# VGA.net
KiCad netlist of a schematic drawn in Altium Designer
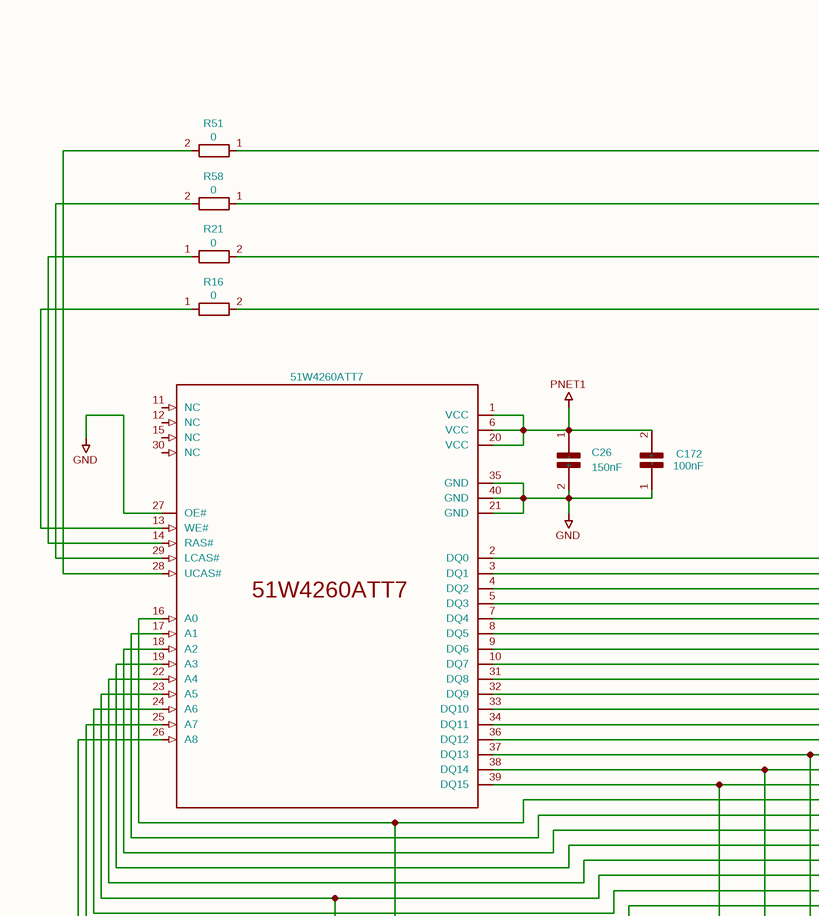
[diagram p0: VGA.SchDoc, top left]
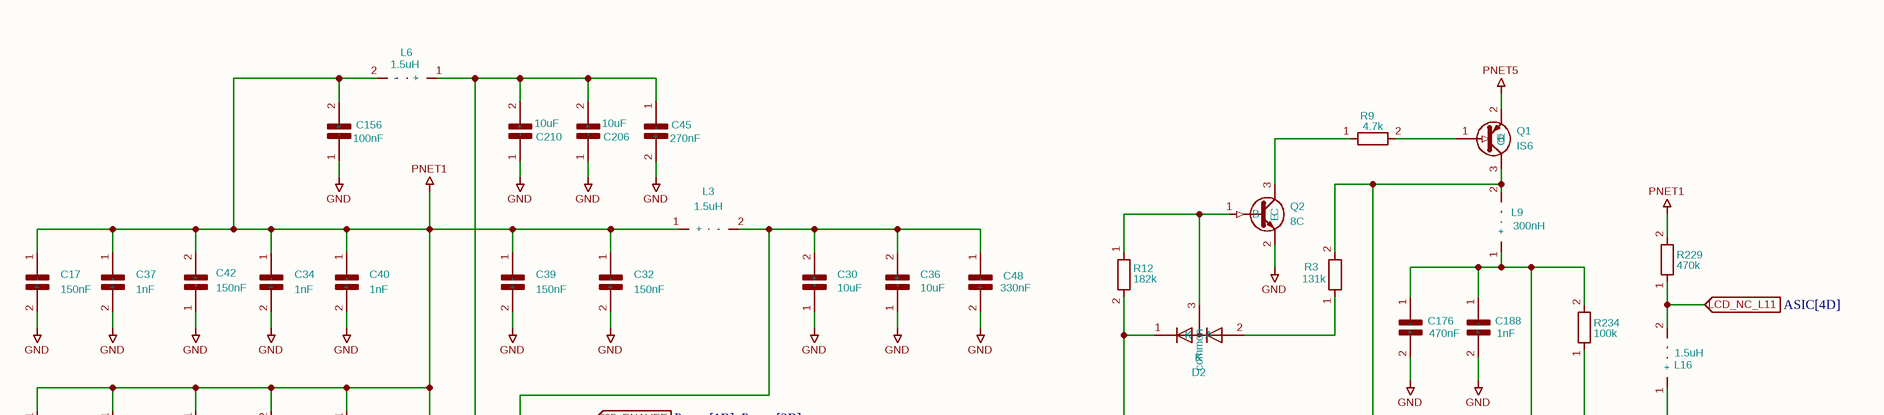
[diagram p1: VGA.SchDoc, top right]
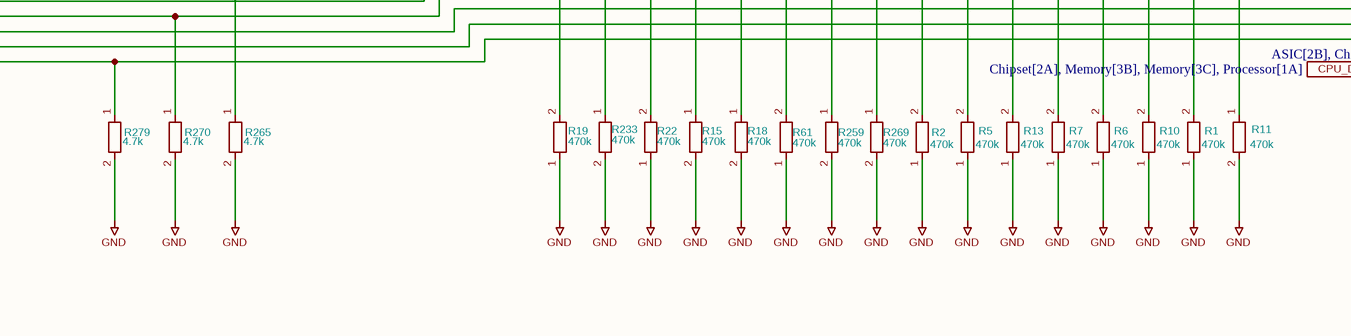
[diagram p2: VGA.SchDoc, bottom left]
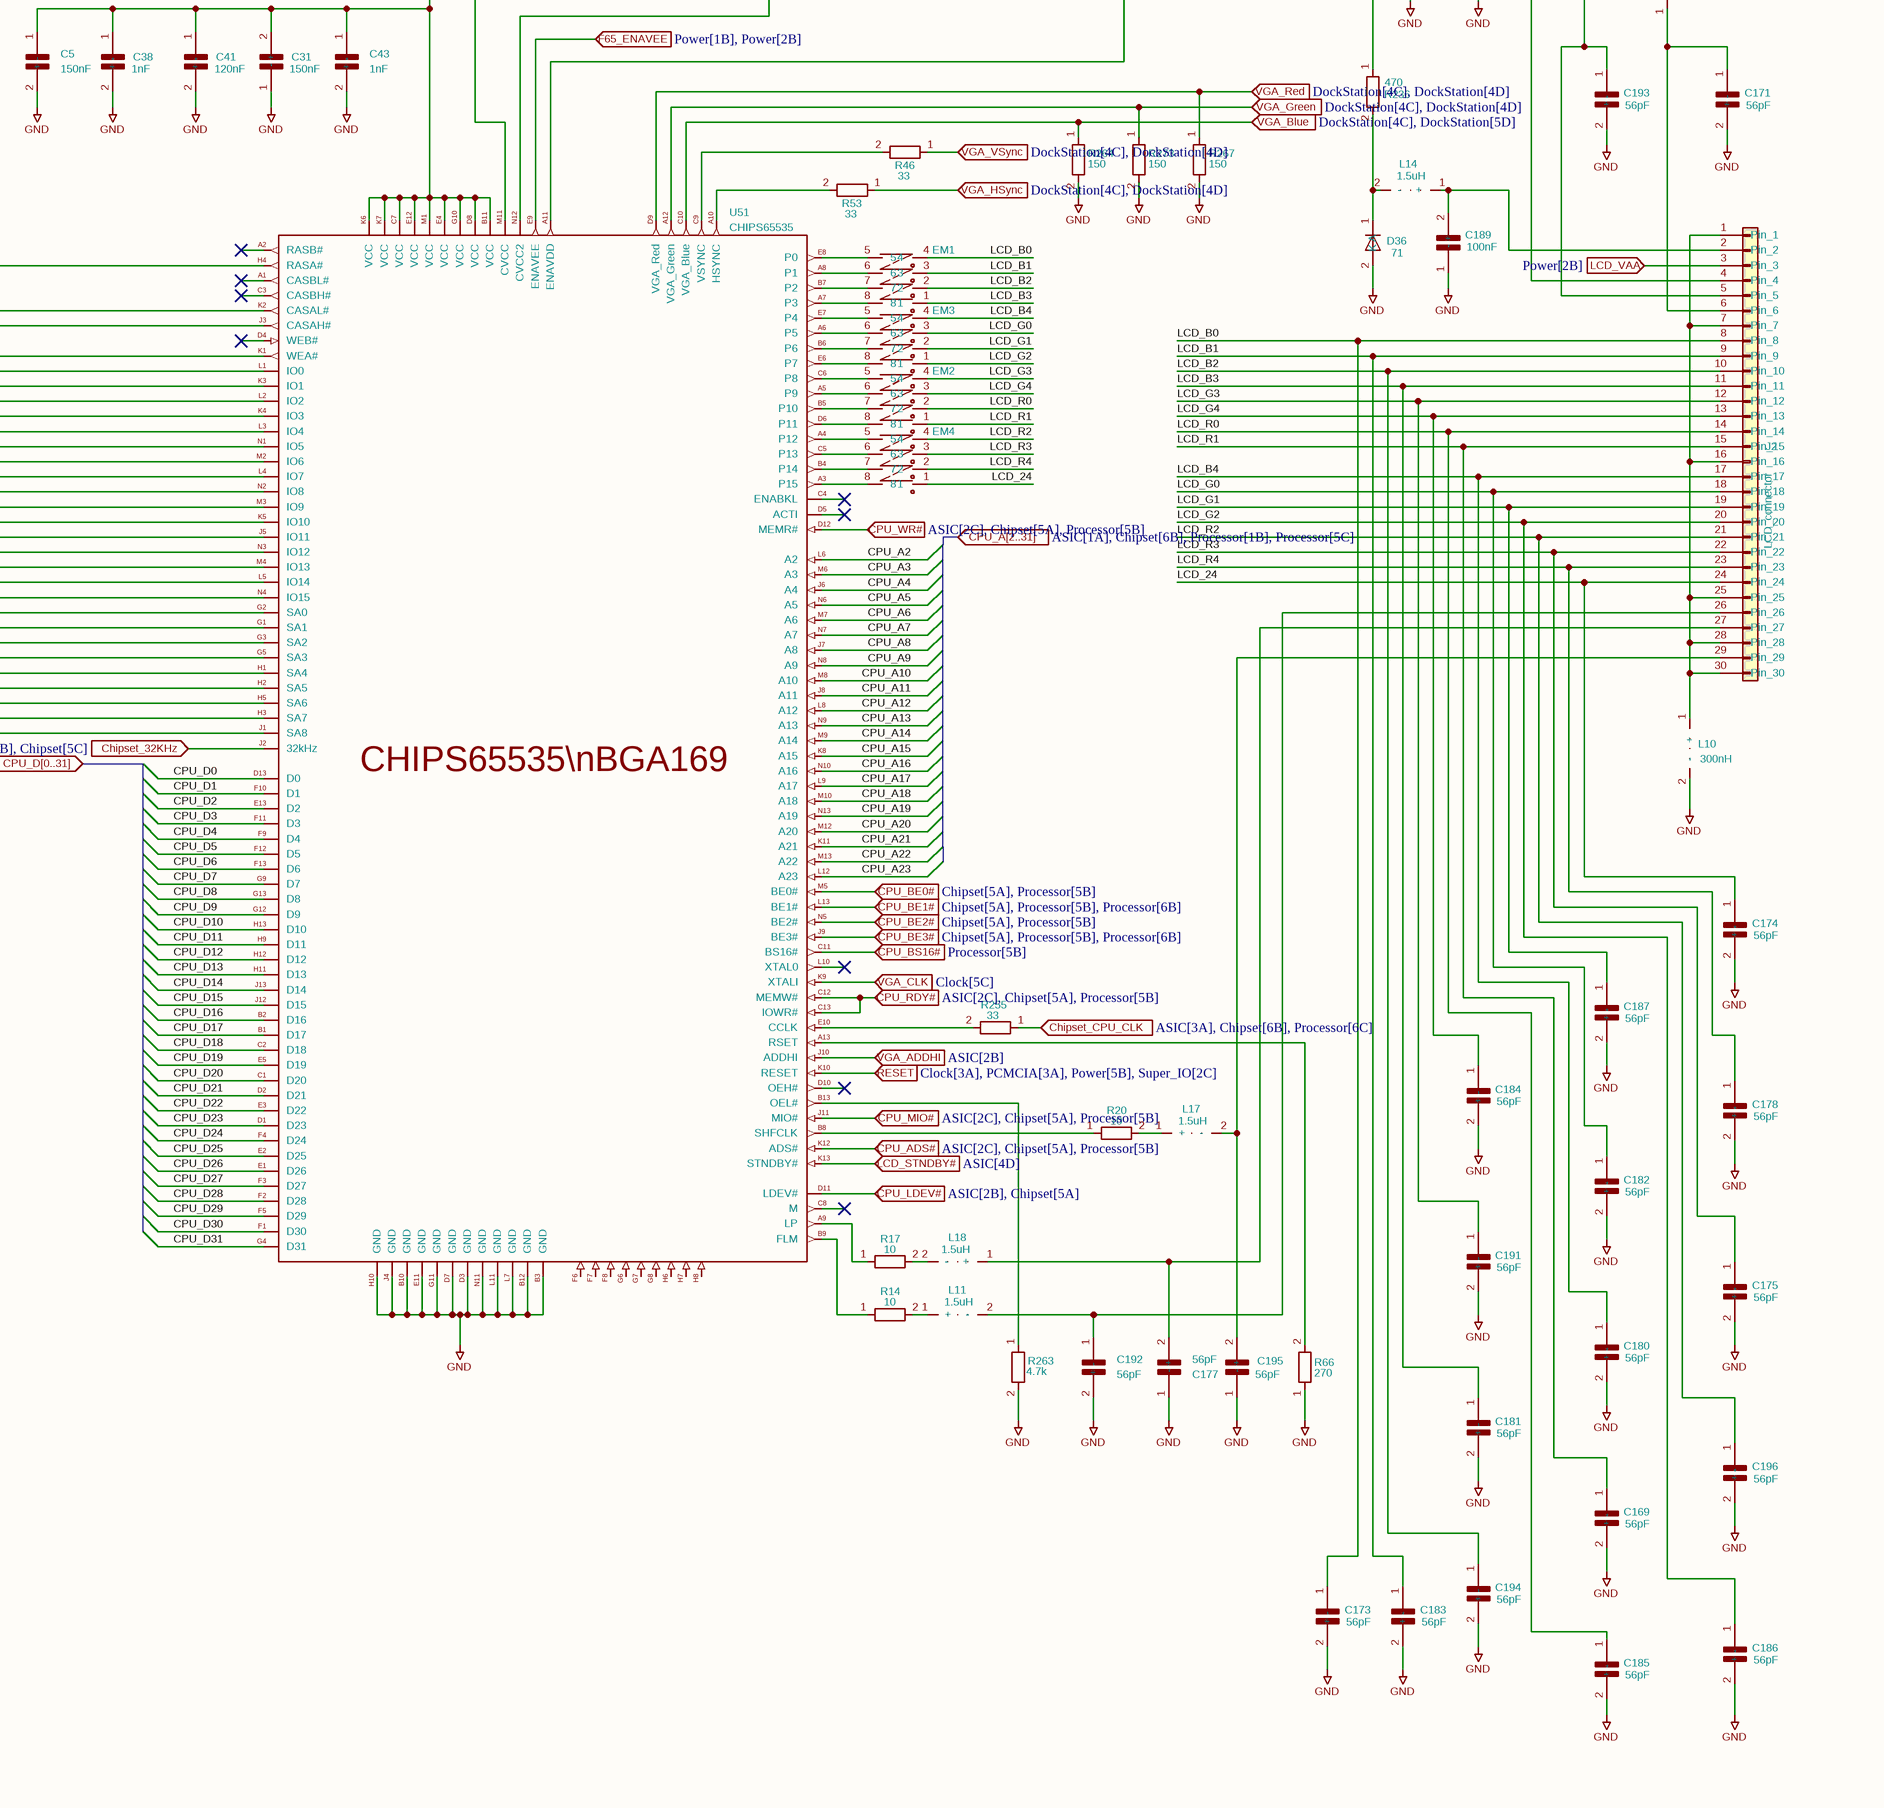
[diagram p3: VGA.SchDoc, bottom right]

(export (version "E")
  (design (tool "Eeschema 10.0.6"))
  (components
    (comp (ref "C5")
      (value "150nF")
      (footprint "C_0402_1005Metric")
      (libsource (lib "PCM_Elektuur") (part "C"))
    )
    (comp (ref "C17")
      (value "150nF")
      (footprint "C_0402_1005Metric")
      (libsource (lib "PCM_Elektuur") (part "C"))
    )
    (comp (ref "C26")
      (value "150nF")
      (footprint "C_0402_1005Metric")
      (libsource (lib "PCM_Elektuur") (part "C"))
    )
    (comp (ref "C30") (value "10uF") (footprint "C_1206_3216Metric") (libsource (lib "") (part "C_1")))
    (comp (ref "C31") (value "150nF") (footprint "C_0402_1005Metric") (libsource (lib "") (part "C_1")))
    (comp (ref "C32")
      (value "150nF")
      (footprint "C_0402_1005Metric")
      (libsource (lib "PCM_Elektuur") (part "C"))
    )
    (comp (ref "C34")
      (value "1nF")
      (footprint "C_0402_1005Metric")
      (libsource (lib "PCM_Elektuur") (part "C"))
    )
    (comp (ref "C36") (value "10uF") (footprint "C_1206_3216Metric") (libsource (lib "") (part "C_1")))
    (comp (ref "C37")
      (value "1nF")
      (footprint "C_0402_1005Metric")
      (libsource (lib "PCM_Elektuur") (part "C"))
    )
    (comp (ref "C38")
      (value "1nF")
      (footprint "C_0402_1005Metric")
      (libsource (lib "PCM_Elektuur") (part "C"))
    )
    (comp (ref "C39")
      (value "150nF")
      (footprint "C_0402_1005Metric")
      (libsource (lib "PCM_Elektuur") (part "C"))
    )
    (comp (ref "C40")
      (value "1nF")
      (footprint "C_0402_1005Metric")
      (libsource (lib "PCM_Elektuur") (part "C"))
    )
    (comp (ref "C41")
      (value "120nF")
      (footprint "C_0402_1005Metric")
      (libsource (lib "PCM_Elektuur") (part "C"))
    )
    (comp (ref "C42") (value "150nF") (footprint "C_0402_1005Metric") (libsource (lib "") (part "C_1")))
    (comp (ref "C43")
      (value "1nF")
      (footprint "C_0402_1005Metric")
      (libsource (lib "PCM_Elektuur") (part "C"))
    )
    (comp (ref "C45")
      (value "270nF")
      (footprint "C_0603_1608Metric")
      (libsource (lib "PCM_Elektuur") (part "C"))
    )
    (comp (ref "C48")
      (value "330nF")
      (footprint "C_0402_1005Metric")
      (libsource (lib "PCM_Elektuur") (part "C"))
    )
    (comp (ref "C156") (value "100nF") (footprint "C_0402_1005Metric") (libsource (lib "") (part "C_1")))
    (comp (ref "C169")
      (value "56pF")
      (footprint "C_0402_1005Metric")
      (libsource (lib "PCM_Elektuur") (part "C"))
    )
    (comp (ref "C171")
      (value "56pF")
      (footprint "C_0402_1005Metric")
      (libsource (lib "PCM_Elektuur") (part "C"))
    )
    (comp (ref "C172") (value "100nF") (footprint "C_0402_1005Metric") (libsource (lib "") (part "C_1")))
    (comp (ref "C173")
      (value "56pF")
      (footprint "C_0402_1005Metric")
      (libsource (lib "PCM_Elektuur") (part "C"))
    )
    (comp (ref "C174")
      (value "56pF")
      (footprint "C_0402_1005Metric")
      (libsource (lib "PCM_Elektuur") (part "C"))
    )
    (comp (ref "C175")
      (value "56pF")
      (footprint "C_0402_1005Metric")
      (libsource (lib "PCM_Elektuur") (part "C"))
    )
    (comp (ref "C176")
      (value "470nF")
      (footprint "C_0603_1608Metric")
      (libsource (lib "PCM_Elektuur") (part "C"))
    )
    (comp (ref "C177") (value "56pF") (footprint "C_0402_1005Metric") (libsource (lib "") (part "C_1")))
    (comp (ref "C178")
      (value "56pF")
      (footprint "C_0402_1005Metric")
      (libsource (lib "PCM_Elektuur") (part "C"))
    )
    (comp (ref "C180")
      (value "56pF")
      (footprint "C_0402_1005Metric")
      (libsource (lib "PCM_Elektuur") (part "C"))
    )
    (comp (ref "C181")
      (value "56pF")
      (footprint "C_0402_1005Metric")
      (libsource (lib "PCM_Elektuur") (part "C"))
    )
    (comp (ref "C182")
      (value "56pF")
      (footprint "C_0402_1005Metric")
      (libsource (lib "PCM_Elektuur") (part "C"))
    )
    (comp (ref "C183")
      (value "56pF")
      (footprint "C_0402_1005Metric")
      (libsource (lib "PCM_Elektuur") (part "C"))
    )
    (comp (ref "C184")
      (value "56pF")
      (footprint "C_0402_1005Metric")
      (libsource (lib "PCM_Elektuur") (part "C"))
    )
    (comp (ref "C185")
      (value "56pF")
      (footprint "C_0402_1005Metric")
      (libsource (lib "PCM_Elektuur") (part "C"))
    )
    (comp (ref "C186")
      (value "56pF")
      (footprint "C_0402_1005Metric")
      (libsource (lib "PCM_Elektuur") (part "C"))
    )
    (comp (ref "C187")
      (value "56pF")
      (footprint "C_0402_1005Metric")
      (libsource (lib "PCM_Elektuur") (part "C"))
    )
    (comp (ref "C188")
      (value "1nF")
      (footprint "C_0402_1005Metric")
      (libsource (lib "PCM_Elektuur") (part "C"))
    )
    (comp (ref "C189") (value "100nF") (footprint "C_0402_1005Metric") (libsource (lib "") (part "C_1")))
    (comp (ref "C191")
      (value "56pF")
      (footprint "C_0402_1005Metric")
      (libsource (lib "PCM_Elektuur") (part "C"))
    )
    (comp (ref "C192")
      (value "56pF")
      (footprint "C_0402_1005Metric")
      (libsource (lib "PCM_Elektuur") (part "C"))
    )
    (comp (ref "C193")
      (value "56pF")
      (footprint "C_0402_1005Metric")
      (libsource (lib "PCM_Elektuur") (part "C"))
    )
    (comp (ref "C194")
      (value "56pF")
      (footprint "C_0402_1005Metric")
      (libsource (lib "PCM_Elektuur") (part "C"))
    )
    (comp (ref "C195") (value "56pF") (footprint "C_0402_1005Metric") (libsource (lib "") (part "C_1")))
    (comp (ref "C196")
      (value "56pF")
      (footprint "C_0402_1005Metric")
      (libsource (lib "PCM_Elektuur") (part "C"))
    )
    (comp (ref "C206") (value "10uF") (footprint "C_1206_3216Metric") (libsource (lib "") (part "C_1")))
    (comp (ref "C210") (value "10uF") (footprint "C_1206_3216Metric") (libsource (lib "") (part "C_1")))
    (comp (ref "D2") (value "K") (footprint "SOT-416L") (libsource (lib "Device") (part "D_Dual_Series_KAC")))
    (comp (ref "D36") (value "71") (footprint "D_0603_1608Metric") (libsource (lib "Device") (part "D")))
    (comp (ref "EM1")
      (value "R-array")
      (footprint "R-array")
      (libsource (lib "PC110") (part "EMI_filter_Array"))
    )
    (comp (ref "EM2")
      (value "R-array")
      (footprint "R-array")
      (libsource (lib "*") (part "EMI_filter_Array_2"))
    )
    (comp (ref "EM3")
      (value "R-array")
      (footprint "R-array")
      (libsource (lib "*") (part "EMI_filter_Array_1"))
    )
    (comp (ref "EM4")
      (value "R-array")
      (footprint "R-array")
      (libsource (lib "*") (part "EMI_filter_Array_3"))
    )
    (comp (ref "J2")
      (value "LCD_connector")
      (footprint "LCD_connector")
      (libsource (lib "Connector_Generic") (part "Conn_01x30"))
    )
    (comp (ref "L3")
      (value "1.5uH")
      (footprint "L_0603_1608Metric")
      (libsource (lib "PCM_Elektuur") (part "L"))
    )
    (comp (ref "L6")
      (value "1.5uH")
      (footprint "L_0603_1608Metric")
      (libsource (lib "PCM_Elektuur") (part "L"))
    )
    (comp (ref "L9")
      (value "300nH")
      (footprint "L_0805_2012Metric")
      (libsource (lib "PCM_Elektuur") (part "L"))
    )
    (comp (ref "L10")
      (value "300nH")
      (footprint "L_0805_2012Metric")
      (libsource (lib "PCM_Elektuur") (part "L"))
    )
    (comp (ref "L11")
      (value "1.5uH")
      (footprint "L_0603_1608Metric")
      (libsource (lib "PCM_Elektuur") (part "L"))
    )
    (comp (ref "L14")
      (value "1.5uH")
      (footprint "L_0603_1608Metric")
      (libsource (lib "PCM_Elektuur") (part "L"))
    )
    (comp (ref "L16")
      (value "1.5uH")
      (footprint "L_0603_1608Metric")
      (libsource (lib "PCM_Elektuur") (part "L"))
    )
    (comp (ref "L17")
      (value "1.5uH")
      (footprint "L_0603_1608Metric")
      (libsource (lib "PCM_Elektuur") (part "L"))
    )
    (comp (ref "L18")
      (value "1.5uH")
      (footprint "L_0603_1608Metric")
      (libsource (lib "PCM_Elektuur") (part "L"))
    )
    (comp (ref "Q1")
      (value "IS6")
      (footprint "SOT-23")
      (libsource (lib "PCM_Transistor_BJT_AKL") (part "Q_PNP_Generic_BEC"))
    )
    (comp (ref "Q2") (value "8C") (footprint "SOT-416") (libsource (lib "Transistor_BJT") (part "MMBTA44")))
    (comp (ref "R1") (value "470k") (footprint "R_0402_1005Metric") (libsource (lib "") (part "R_2")))
    (comp (ref "R2") (value "470k") (footprint "R_0402_1005Metric") (libsource (lib "") (part "R_2")))
    (comp (ref "R3") (value "131k") (footprint "R_0402_1005Metric") (libsource (lib "") (part "R_1")))
    (comp (ref "R5") (value "470k") (footprint "R_0402_1005Metric") (libsource (lib "") (part "R_2")))
    (comp (ref "R6") (value "470k") (footprint "R_0402_1005Metric") (libsource (lib "") (part "R_2")))
    (comp (ref "R7") (value "470k") (footprint "R_0402_1005Metric") (libsource (lib "") (part "R_2")))
    (comp (ref "R9") (value "4.7k") (footprint "R_0402_1005Metric") (libsource (lib "") (part "R_2")))
    (comp (ref "R10") (value "470k") (footprint "R_0402_1005Metric") (libsource (lib "") (part "R_2")))
    (comp (ref "R11") (value "470k") (footprint "R_0402_1005Metric") (libsource (lib "Device") (part "R")))
    (comp (ref "R12") (value "182k") (footprint "R_0402_1005Metric") (libsource (lib "Device") (part "R")))
    (comp (ref "R13") (value "470k") (footprint "R_0402_1005Metric") (libsource (lib "") (part "R_2")))
    (comp (ref "R14") (value "10") (footprint "R_0402_1005Metric") (libsource (lib "") (part "R_2")))
    (comp (ref "R15") (value "470k") (footprint "R_0402_1005Metric") (libsource (lib "Device") (part "R")))
    (comp (ref "R16") (value "0") (footprint "R_0402_1005Metric") (libsource (lib "") (part "R_2")))
    (comp (ref "R17") (value "10") (footprint "R_0402_1005Metric") (libsource (lib "") (part "R_2")))
    (comp (ref "R18") (value "470k") (footprint "R_0402_1005Metric") (libsource (lib "Device") (part "R")))
    (comp (ref "R19") (value "470k") (footprint "R_0402_1005Metric") (libsource (lib "") (part "R_2")))
    (comp (ref "R20") (value "10") (footprint "R_0402_1005Metric") (libsource (lib "") (part "R_2")))
    (comp (ref "R21") (value "0") (footprint "R_0402_1005Metric") (libsource (lib "") (part "R_2")))
    (comp (ref "R22") (value "470k") (footprint "R_0402_1005Metric") (libsource (lib "") (part "R_2")))
    (comp (ref "R46") (value "33") (footprint "R_0402_1005Metric") (libsource (lib "Device") (part "R")))
    (comp (ref "R51") (value "0") (footprint "R_0402_1005Metric") (libsource (lib "Device") (part "R")))
    (comp (ref "R53") (value "33") (footprint "R_0402_1005Metric") (libsource (lib "Device") (part "R")))
    (comp (ref "R58") (value "0") (footprint "R_0402_1005Metric") (libsource (lib "Device") (part "R")))
    (comp (ref "R61") (value "470k") (footprint "R_0402_1005Metric") (libsource (lib "") (part "R_2")))
    (comp (ref "R66") (value "270") (footprint "R_0402_1005Metric") (libsource (lib "") (part "R_2")))
    (comp (ref "R229") (value "470k") (footprint "R_0402_1005Metric") (libsource (lib "") (part "R_2")))
    (comp (ref "R233") (value "470k") (footprint "R_0402_1005Metric") (libsource (lib "Device") (part "R")))
    (comp (ref "R234") (value "100k") (footprint "R_0402_1005Metric") (libsource (lib "") (part "R_2")))
    (comp (ref "R236") (value "470") (footprint "R_0402_1005Metric") (libsource (lib "") (part "R_3")))
    (comp (ref "R255") (value "33") (footprint "R_0402_1005Metric") (libsource (lib "Device") (part "R")))
    (comp (ref "R259") (value "470k") (footprint "R_0402_1005Metric") (libsource (lib "Device") (part "R")))
    (comp (ref "R263") (value "4.7k") (footprint "R_0402_1005Metric") (libsource (lib "Device") (part "R")))
    (comp (ref "R264") (value "150") (footprint "R_0805_2012Metric") (libsource (lib "Device") (part "R")))
    (comp (ref "R265") (value "4.7k") (footprint "R_0402_1005Metric") (libsource (lib "Device") (part "R")))
    (comp (ref "R267") (value "150") (footprint "R_0805_2012Metric") (libsource (lib "Device") (part "R")))
    (comp (ref "R269") (value "470k") (footprint "R_0402_1005Metric") (libsource (lib "Device") (part "R")))
    (comp (ref "R270") (value "4.7k") (footprint "R_0402_1005Metric") (libsource (lib "Device") (part "R")))
    (comp (ref "R273") (value "150") (footprint "R_0805_2012Metric") (libsource (lib "Device") (part "R")))
    (comp (ref "R279") (value "4.7k") (footprint "R_0402_1005Metric") (libsource (lib "Device") (part "R")))
    (comp (ref "U8") (value "51W4260ATT7") (footprint "GRAMchip") (libsource (lib "PC110") (part "51W4260")))
    (comp (ref "U51") (value "CHIPS65535") (footprint "BGA-169") (libsource (lib "PC110") (part "65535")))
  )
  (nets
    (net (code "9") (name "/CPU_A2") (class "Default")
      (node (ref "U51") (pin "L6") (pinfunction "A2_L6") (pintype "input"))
    )
    (net (code "10") (name "/CPU_A3") (class "Default")
      (node (ref "U51") (pin "M6") (pinfunction "A3_M6") (pintype "input"))
    )
    (net (code "11") (name "/CPU_A4") (class "Default")
      (node (ref "U51") (pin "J6") (pinfunction "A4_J6") (pintype "input"))
    )
    (net (code "12") (name "/CPU_A5") (class "Default")
      (node (ref "U51") (pin "N6") (pinfunction "A5_N6") (pintype "input"))
    )
    (net (code "13") (name "/CPU_A6") (class "Default")
      (node (ref "U51") (pin "M7") (pinfunction "A6_M7") (pintype "input"))
    )
    (net (code "14") (name "/CPU_A7") (class "Default")
      (node (ref "U51") (pin "N7") (pinfunction "A7_N7") (pintype "input"))
    )
    (net (code "15") (name "/CPU_A8") (class "Default")
      (node (ref "U51") (pin "J7") (pinfunction "A8_J7") (pintype "input"))
    )
    (net (code "16") (name "/CPU_A9") (class "Default")
      (node (ref "U51") (pin "N8") (pinfunction "A9_N8") (pintype "input"))
    )
    (net (code "17") (name "/CPU_A10") (class "Default")
      (node (ref "U51") (pin "M8") (pinfunction "A10_M8") (pintype "input"))
    )
    (net (code "18") (name "/CPU_A11") (class "Default")
      (node (ref "U51") (pin "J8") (pinfunction "A11_J8") (pintype "input"))
    )
    (net (code "19") (name "/CPU_A12") (class "Default")
      (node (ref "U51") (pin "L8") (pinfunction "A12_L8") (pintype "input"))
    )
    (net (code "20") (name "/CPU_A13") (class "Default")
      (node (ref "U51") (pin "N9") (pinfunction "A13_N9") (pintype "input"))
    )
    (net (code "21") (name "/CPU_A14") (class "Default")
      (node (ref "U51") (pin "M9") (pinfunction "A14_M9") (pintype "input"))
    )
    (net (code "22") (name "/CPU_A15") (class "Default")
      (node (ref "U51") (pin "K8") (pinfunction "A15_K8") (pintype "input"))
    )
    (net (code "23") (name "/CPU_A16") (class "Default")
      (node (ref "U51") (pin "N10") (pinfunction "A16_N10") (pintype "input"))
    )
    (net (code "24") (name "/CPU_A17") (class "Default")
      (node (ref "U51") (pin "L9") (pinfunction "A17_L9") (pintype "input"))
    )
    (net (code "25") (name "/CPU_A18") (class "Default")
      (node (ref "U51") (pin "M10") (pinfunction "A18_M10") (pintype "input"))
    )
    (net (code "26") (name "/CPU_A19") (class "Default")
      (node (ref "U51") (pin "N13") (pinfunction "A19_N13") (pintype "input"))
    )
    (net (code "27") (name "/CPU_A20") (class "Default")
      (node (ref "U51") (pin "M12") (pinfunction "A20_M12") (pintype "input"))
    )
    (net (code "28") (name "/CPU_A21") (class "Default")
      (node (ref "U51") (pin "K11") (pinfunction "A21_K11") (pintype "input"))
    )
    (net (code "29") (name "/CPU_A22") (class "Default")
      (node (ref "U51") (pin "M13") (pinfunction "A22_M13") (pintype "input"))
    )
    (net (code "30") (name "/CPU_A23") (class "Default")
      (node (ref "U51") (pin "L12") (pinfunction "A23_L12") (pintype "input"))
    )
    (net (code "31") (name "/CPU_ADS#") (class "Default")
      (node (ref "U51") (pin "K12") (pinfunction "ADS#_K12") (pintype "input"))
    )
    (net (code "33") (name "/CPU_BE0#") (class "Default")
      (node (ref "U51") (pin "M5") (pinfunction "BE0#_M5") (pintype "input"))
    )
    (net (code "34") (name "/CPU_BE1#") (class "Default")
      (node (ref "U51") (pin "L13") (pinfunction "BE1#_L13") (pintype "input"))
    )
    (net (code "35") (name "/CPU_BE2#") (class "Default")
      (node (ref "U51") (pin "N5") (pinfunction "BE2#_N5") (pintype "input"))
    )
    (net (code "36") (name "/CPU_BE3#") (class "Default")
      (node (ref "U51") (pin "J9") (pinfunction "BE3#_J9") (pintype "input"))
    )
    (net (code "37") (name "/CPU_BS16#") (class "Default")
      (node (ref "U51") (pin "C11") (pinfunction "BS16#_C11") (pintype "output"))
    )
    (net (code "38") (name "/CPU_D0") (class "Default")
      (node (ref "U51") (pin "D13") (pinfunction "D0_D13") (pintype "bidirectional"))
    )
    (net (code "39") (name "/CPU_D1") (class "Default")
      (node (ref "U51") (pin "F10") (pinfunction "D1_F10") (pintype "bidirectional"))
    )
    (net (code "40") (name "/CPU_D2") (class "Default")
      (node (ref "U51") (pin "E13") (pinfunction "D2_E13") (pintype "bidirectional"))
    )
    (net (code "41") (name "/CPU_D3") (class "Default")
      (node (ref "U51") (pin "F11") (pinfunction "D3_F11") (pintype "bidirectional"))
    )
    (net (code "42") (name "/CPU_D4") (class "Default")
      (node (ref "U51") (pin "F9") (pinfunction "D4_F9") (pintype "bidirectional"))
    )
    (net (code "43") (name "/CPU_D5") (class "Default")
      (node (ref "U51") (pin "F12") (pinfunction "D5_F12") (pintype "bidirectional"))
    )
    (net (code "44") (name "/CPU_D6") (class "Default")
      (node (ref "U51") (pin "F13") (pinfunction "D6_F13") (pintype "bidirectional"))
    )
    (net (code "45") (name "/CPU_D7") (class "Default")
      (node (ref "U51") (pin "G9") (pinfunction "D7_G9") (pintype "bidirectional"))
    )
    (net (code "46") (name "/CPU_D8") (class "Default")
      (node (ref "U51") (pin "G13") (pinfunction "D8_G13") (pintype "bidirectional"))
    )
    (net (code "47") (name "/CPU_D9") (class "Default")
      (node (ref "U51") (pin "G12") (pinfunction "D9_G12") (pintype "bidirectional"))
    )
    (net (code "48") (name "/CPU_D10") (class "Default")
      (node (ref "U51") (pin "H13") (pinfunction "D10_H13") (pintype "bidirectional"))
    )
    (net (code "49") (name "/CPU_D11") (class "Default")
      (node (ref "U51") (pin "H9") (pinfunction "D11_H9") (pintype "bidirectional"))
    )
    (net (code "50") (name "/CPU_D12") (class "Default")
      (node (ref "U51") (pin "H12") (pinfunction "D12_H12") (pintype "bidirectional"))
    )
    (net (code "51") (name "/CPU_D13") (class "Default")
      (node (ref "U51") (pin "H11") (pinfunction "D13_H11") (pintype "bidirectional"))
    )
    (net (code "52") (name "/CPU_D14") (class "Default")
      (node (ref "U51") (pin "J13") (pinfunction "D14_J13") (pintype "bidirectional"))
    )
    (net (code "53") (name "/CPU_D15") (class "Default")
      (node (ref "U51") (pin "J12") (pinfunction "D15_J12") (pintype "bidirectional"))
    )
    (net (code "54") (name "/CPU_D16") (class "Default")
      (node (ref "U51") (pin "B2") (pinfunction "D16_B2") (pintype "bidirectional"))
    )
    (net (code "55") (name "/CPU_D17") (class "Default")
      (node (ref "U51") (pin "B1") (pinfunction "D17_B1") (pintype "bidirectional"))
    )
    (net (code "56") (name "/CPU_D18") (class "Default")
      (node (ref "U51") (pin "C2") (pinfunction "D18_C2") (pintype "bidirectional"))
    )
    (net (code "57") (name "/CPU_D19") (class "Default")
      (node (ref "U51") (pin "E5") (pinfunction "D19_E5") (pintype "bidirectional"))
    )
    (net (code "58") (name "/CPU_D20") (class "Default")
      (node (ref "U51") (pin "C1") (pinfunction "D20_C1") (pintype "bidirectional"))
    )
    (net (code "59") (name "/CPU_D21") (class "Default")
      (node (ref "U51") (pin "D2") (pinfunction "D21_D2") (pintype "bidirectional"))
    )
    (net (code "60") (name "/CPU_D22") (class "Default")
      (node (ref "U51") (pin "E3") (pinfunction "D22_E3") (pintype "bidirectional"))
    )
    (net (code "61") (name "/CPU_D23") (class "Default")
      (node (ref "U51") (pin "D1") (pinfunction "D23_D1") (pintype "bidirectional"))
    )
    (net (code "62") (name "/CPU_D24") (class "Default")
      (node (ref "U51") (pin "F4") (pinfunction "D24_F4") (pintype "bidirectional"))
    )
    (net (code "63") (name "/CPU_D25") (class "Default")
      (node (ref "U51") (pin "E2") (pinfunction "D25_E2") (pintype "bidirectional"))
    )
    (net (code "64") (name "/CPU_D26") (class "Default")
      (node (ref "U51") (pin "E1") (pinfunction "D26_E1") (pintype "bidirectional"))
    )
    (net (code "65") (name "/CPU_D27") (class "Default")
      (node (ref "U51") (pin "F3") (pinfunction "D27_F3") (pintype "bidirectional"))
    )
    (net (code "66") (name "/CPU_D28") (class "Default")
      (node (ref "U51") (pin "F2") (pinfunction "D28_F2") (pintype "bidirectional"))
    )
    (net (code "67") (name "/CPU_D29") (class "Default")
      (node (ref "U51") (pin "F5") (pinfunction "D29_F5") (pintype "bidirectional"))
    )
    (net (code "68") (name "/CPU_D30") (class "Default")
      (node (ref "U51") (pin "F1") (pinfunction "D30_F1") (pintype "bidirectional"))
    )
    (net (code "69") (name "/CPU_D31") (class "Default")
      (node (ref "U51") (pin "G4") (pinfunction "D31_G4") (pintype "bidirectional"))
    )
    (net (code "71") (name "/CPU_LDEV#") (class "Default")
      (node (ref "U51") (pin "D11") (pinfunction "LDEV#_D11") (pintype "bidirectional"))
    )
    (net (code "72") (name "/CPU_MIO#") (class "Default")
      (node (ref "U51") (pin "J11") (pinfunction "MIO#_J11") (pintype "input"))
    )
    (net (code "73") (name "/CPU_RDY#") (class "Default")
      (node (ref "U51") (pin "C12") (pinfunction "MEMW#_C12") (pintype "input"))
      (node (ref "U51") (pin "C13") (pinfunction "IOWR#_C13") (pintype "input"))
    )
    (net (code "74") (name "/CPU_WR#") (class "Default")
      (node (ref "U51") (pin "D12") (pinfunction "MEMR#_D12") (pintype "input"))
    )
    (net (code "75") (name "/Chipset_32KHz") (class "Default")
      (node (ref "U51") (pin "J2") (pinfunction "32kHz_J2") (pintype "bidirectional"))
    )
    (net (code "76") (name "/Chipset_CPU_CLK") (class "Default")
      (node (ref "R255") (pin "1") (pinfunction "1_1") (pintype "passive"))
    )
    (net (code "77") (name "/F65_ENAVEE") (class "Default")
      (node (ref "U51") (pin "E9") (pinfunction "ENAVEE_E9") (pintype "output"))
    )
    (net (code "78") (name "/LCD_24") (class "Default")
      (node (ref "C174") (pin "1") (pinfunction "+_1") (pintype "passive"))
      (node (ref "EM4") (pin "1") (pinfunction "1_1") (pintype "passive"))
      (node (ref "J2") (pin "24") (pinfunction "Pin_24_24") (pintype "passive"))
    )
    (net (code "79") (name "/LCD_B0") (class "Default")
      (node (ref "C173") (pin "1") (pinfunction "+_1") (pintype "passive"))
      (node (ref "EM1") (pin "4") (pinfunction "4_4") (pintype "passive"))
      (node (ref "J2") (pin "8") (pinfunction "Pin_8_8") (pintype "passive"))
    )
    (net (code "80") (name "/LCD_B1") (class "Default")
      (node (ref "C183") (pin "1") (pinfunction "+_1") (pintype "passive"))
      (node (ref "EM1") (pin "3") (pinfunction "3_3") (pintype "passive"))
      (node (ref "J2") (pin "9") (pinfunction "Pin_9_9") (pintype "passive"))
    )
    (net (code "81") (name "/LCD_B2") (class "Default")
      (node (ref "C194") (pin "1") (pinfunction "+_1") (pintype "passive"))
      (node (ref "EM1") (pin "2") (pinfunction "2_2") (pintype "passive"))
      (node (ref "J2") (pin "10") (pinfunction "Pin_10_10") (pintype "passive"))
    )
    (net (code "82") (name "/LCD_B3") (class "Default")
      (node (ref "C181") (pin "1") (pinfunction "+_1") (pintype "passive"))
      (node (ref "EM1") (pin "1") (pinfunction "1_1") (pintype "passive"))
      (node (ref "J2") (pin "11") (pinfunction "Pin_11_11") (pintype "passive"))
    )
    (net (code "83") (name "/LCD_B4") (class "Default")
      (node (ref "C180") (pin "1") (pinfunction "+_1") (pintype "passive"))
      (node (ref "EM3") (pin "4") (pinfunction "4_4") (pintype "passive"))
      (node (ref "J2") (pin "17") (pinfunction "Pin_17_17") (pintype "passive"))
    )
    (net (code "84") (name "/LCD_G0") (class "Default")
      (node (ref "C182") (pin "1") (pinfunction "+_1") (pintype "passive"))
      (node (ref "EM3") (pin "3") (pinfunction "3_3") (pintype "passive"))
      (node (ref "J2") (pin "18") (pinfunction "Pin_18_18") (pintype "passive"))
    )
    (net (code "85") (name "/LCD_G1") (class "Default")
      (node (ref "C187") (pin "1") (pinfunction "+_1") (pintype "passive"))
      (node (ref "EM3") (pin "2") (pinfunction "2_2") (pintype "passive"))
      (node (ref "J2") (pin "19") (pinfunction "Pin_19_19") (pintype "passive"))
    )
    (net (code "86") (name "/LCD_G2") (class "Default")
      (node (ref "C186") (pin "1") (pinfunction "+_1") (pintype "passive"))
      (node (ref "EM3") (pin "1") (pinfunction "1_1") (pintype "passive"))
      (node (ref "J2") (pin "20") (pinfunction "Pin_20_20") (pintype "passive"))
    )
    (net (code "87") (name "/LCD_G3") (class "Default")
      (node (ref "C191") (pin "1") (pinfunction "+_1") (pintype "passive"))
      (node (ref "EM2") (pin "4") (pinfunction "4_4") (pintype "passive"))
      (node (ref "J2") (pin "12") (pinfunction "Pin_12_12") (pintype "passive"))
    )
    (net (code "88") (name "/LCD_G4") (class "Default")
      (node (ref "C184") (pin "1") (pinfunction "+_1") (pintype "passive"))
      (node (ref "EM2") (pin "3") (pinfunction "3_3") (pintype "passive"))
      (node (ref "J2") (pin "13") (pinfunction "Pin_13_13") (pintype "passive"))
    )
    (net (code "89") (name "/LCD_NC_L11") (class "Default")
      (node (ref "L16") (pin "2") (pinfunction "-_2") (pintype "passive"))
      (node (ref "R229") (pin "1") (pinfunction "1_1") (pintype "passive"))
    )
    (net (code "90") (name "/LCD_R0") (class "Default")
      (node (ref "C185") (pin "1") (pinfunction "+_1") (pintype "passive"))
      (node (ref "EM2") (pin "2") (pinfunction "2_2") (pintype "passive"))
      (node (ref "J2") (pin "14") (pinfunction "Pin_14_14") (pintype "passive"))
    )
    (net (code "91") (name "/LCD_R1") (class "Default")
      (node (ref "C169") (pin "1") (pinfunction "+_1") (pintype "passive"))
      (node (ref "EM2") (pin "1") (pinfunction "1_1") (pintype "passive"))
      (node (ref "J2") (pin "15") (pinfunction "Pin_15_15") (pintype "passive"))
    )
    (net (code "92") (name "/LCD_R2") (class "Default")
      (node (ref "C196") (pin "1") (pinfunction "+_1") (pintype "passive"))
      (node (ref "EM4") (pin "4") (pinfunction "4_4") (pintype "passive"))
      (node (ref "J2") (pin "21") (pinfunction "Pin_21_21") (pintype "passive"))
    )
    (net (code "93") (name "/LCD_R3") (class "Default")
      (node (ref "C175") (pin "1") (pinfunction "+_1") (pintype "passive"))
      (node (ref "EM4") (pin "3") (pinfunction "3_3") (pintype "passive"))
      (node (ref "J2") (pin "22") (pinfunction "Pin_22_22") (pintype "passive"))
    )
    (net (code "94") (name "/LCD_R4") (class "Default")
      (node (ref "C178") (pin "1") (pinfunction "+_1") (pintype "passive"))
      (node (ref "EM4") (pin "2") (pinfunction "2_2") (pintype "passive"))
      (node (ref "J2") (pin "23") (pinfunction "Pin_23_23") (pintype "passive"))
    )
    (net (code "95") (name "/LCD_STNDBY#") (class "Default")
      (node (ref "U51") (pin "K13") (pinfunction "STNDBY#_K13") (pintype "input"))
    )
    (net (code "96") (name "/LCD_VAA") (class "Default")
      (node (ref "J2") (pin "3") (pinfunction "Pin_3_3") (pintype "passive"))
    )
    (net (code "97") (name "/RESET") (class "Default")
      (node (ref "U51") (pin "K10") (pinfunction "RESET_K10") (pintype "input"))
    )
    (net (code "98") (name "/VGA_ADDHI") (class "Default")
      (node (ref "U51") (pin "J10") (pinfunction "ADDHI_J10") (pintype "input"))
    )
    (net (code "99") (name "/VGA_Blue") (class "Default")
      (node (ref "R264") (pin "1") (pinfunction "1_1") (pintype "passive"))
      (node (ref "U51") (pin "C10") (pinfunction "VGA_Blue_C10") (pintype "output"))
    )
    (net (code "100") (name "/VGA_CLK") (class "Default")
      (node (ref "U51") (pin "K9") (pinfunction "XTALI_K9") (pintype "input"))
    )
    (net (code "101") (name "/VGA_Green") (class "Default")
      (node (ref "R273") (pin "1") (pinfunction "1_1") (pintype "passive"))
      (node (ref "U51") (pin "A12") (pinfunction "VGA_Green_A12") (pintype "output"))
    )
    (net (code "102") (name "/VGA_HSync") (class "Default")
      (node (ref "R53") (pin "1") (pinfunction "1_1") (pintype "passive"))
    )
    (net (code "103") (name "/VGA_Red") (class "Default")
      (node (ref "R267") (pin "1") (pinfunction "1_1") (pintype "passive"))
      (node (ref "U51") (pin "D9") (pinfunction "VGA_Red_D9") (pintype "output"))
    )
    (net (code "104") (name "/VGA_VSync") (class "Default")
      (node (ref "R46") (pin "1") (pinfunction "1_1") (pintype "passive"))
    )
    (net (code "105") (name "GND") (class "Default")
      (node (ref "C156") (pin "1") (pinfunction "+_1") (pintype "passive"))
      (node (ref "C169") (pin "2") (pinfunction "-_2") (pintype "passive"))
      (node (ref "C17") (pin "2") (pinfunction "-_2") (pintype "passive"))
      (node (ref "C171") (pin "2") (pinfunction "-_2") (pintype "passive"))
      (node (ref "C172") (pin "1") (pinfunction "+_1") (pintype "passive"))
      (node (ref "C173") (pin "2") (pinfunction "-_2") (pintype "passive"))
      (node (ref "C174") (pin "2") (pinfunction "-_2") (pintype "passive"))
      (node (ref "C175") (pin "2") (pinfunction "-_2") (pintype "passive"))
      (node (ref "C176") (pin "2") (pinfunction "-_2") (pintype "passive"))
      (node (ref "C177") (pin "1") (pinfunction "+_1") (pintype "passive"))
      (node (ref "C178") (pin "2") (pinfunction "-_2") (pintype "passive"))
      (node (ref "C180") (pin "2") (pinfunction "-_2") (pintype "passive"))
      (node (ref "C181") (pin "2") (pinfunction "-_2") (pintype "passive"))
      (node (ref "C182") (pin "2") (pinfunction "-_2") (pintype "passive"))
      (node (ref "C183") (pin "2") (pinfunction "-_2") (pintype "passive"))
      (node (ref "C184") (pin "2") (pinfunction "-_2") (pintype "passive"))
      (node (ref "C185") (pin "2") (pinfunction "-_2") (pintype "passive"))
      (node (ref "C186") (pin "2") (pinfunction "-_2") (pintype "passive"))
      (node (ref "C187") (pin "2") (pinfunction "-_2") (pintype "passive"))
      (node (ref "C188") (pin "2") (pinfunction "-_2") (pintype "passive"))
      (node (ref "C189") (pin "1") (pinfunction "+_1") (pintype "passive"))
      (node (ref "C191") (pin "2") (pinfunction "-_2") (pintype "passive"))
      (node (ref "C192") (pin "2") (pinfunction "-_2") (pintype "passive"))
      (node (ref "C193") (pin "2") (pinfunction "-_2") (pintype "passive"))
      (node (ref "C194") (pin "2") (pinfunction "-_2") (pintype "passive"))
      (node (ref "C195") (pin "1") (pinfunction "+_1") (pintype "passive"))
      (node (ref "C196") (pin "2") (pinfunction "-_2") (pintype "passive"))
      (node (ref "C206") (pin "1") (pinfunction "+_1") (pintype "passive"))
      (node (ref "C210") (pin "1") (pinfunction "+_1") (pintype "passive"))
      (node (ref "C26") (pin "2") (pinfunction "-_2") (pintype "passive"))
      (node (ref "C30") (pin "1") (pinfunction "+_1") (pintype "passive"))
      (node (ref "C31") (pin "1") (pinfunction "+_1") (pintype "passive"))
      (node (ref "C32") (pin "2") (pinfunction "-_2") (pintype "passive"))
      (node (ref "C34") (pin "2") (pinfunction "-_2") (pintype "passive"))
      (node (ref "C36") (pin "1") (pinfunction "+_1") (pintype "passive"))
      (node (ref "C37") (pin "2") (pinfunction "-_2") (pintype "passive"))
      (node (ref "C38") (pin "2") (pinfunction "-_2") (pintype "passive"))
      (node (ref "C39") (pin "2") (pinfunction "-_2") (pintype "passive"))
      (node (ref "C40") (pin "2") (pinfunction "-_2") (pintype "passive"))
      (node (ref "C41") (pin "2") (pinfunction "-_2") (pintype "passive"))
      (node (ref "C42") (pin "1") (pinfunction "+_1") (pintype "passive"))
      (node (ref "C43") (pin "2") (pinfunction "-_2") (pintype "passive"))
      (node (ref "C45") (pin "2") (pinfunction "-_2") (pintype "passive"))
      (node (ref "C48") (pin "2") (pinfunction "-_2") (pintype "passive"))
      (node (ref "C5") (pin "2") (pinfunction "-_2") (pintype "passive"))
      (node (ref "D36") (pin "2") (pinfunction "A_2") (pintype "passive"))
      (node (ref "L10") (pin "2") (pinfunction "-_2") (pintype "passive"))
      (node (ref "Q2") (pin "2") (pinfunction "E_2") (pintype "passive"))
      (node (ref "R1") (pin "1") (pinfunction "1_1") (pintype "passive"))
      (node (ref "R10") (pin "1") (pinfunction "1_1") (pintype "passive"))
      (node (ref "R11") (pin "2") (pinfunction "2_2") (pintype "passive"))
      (node (ref "R13") (pin "1") (pinfunction "1_1") (pintype "passive"))
      (node (ref "R15") (pin "2") (pinfunction "2_2") (pintype "passive"))
      (node (ref "R18") (pin "2") (pinfunction "2_2") (pintype "passive"))
      (node (ref "R19") (pin "1") (pinfunction "1_1") (pintype "passive"))
      (node (ref "R2") (pin "1") (pinfunction "1_1") (pintype "passive"))
      (node (ref "R22") (pin "1") (pinfunction "1_1") (pintype "passive"))
      (node (ref "R233") (pin "2") (pinfunction "2_2") (pintype "passive"))
      (node (ref "R259") (pin "2") (pinfunction "2_2") (pintype "passive"))
      (node (ref "R263") (pin "2") (pinfunction "2_2") (pintype "passive"))
      (node (ref "R264") (pin "2") (pinfunction "2_2") (pintype "passive"))
      (node (ref "R265") (pin "2") (pinfunction "2_2") (pintype "passive"))
      (node (ref "R267") (pin "2") (pinfunction "2_2") (pintype "passive"))
      (node (ref "R269") (pin "2") (pinfunction "2_2") (pintype "passive"))
      (node (ref "R270") (pin "2") (pinfunction "2_2") (pintype "passive"))
      (node (ref "R273") (pin "2") (pinfunction "2_2") (pintype "passive"))
      (node (ref "R279") (pin "2") (pinfunction "2_2") (pintype "passive"))
      (node (ref "R5") (pin "1") (pinfunction "1_1") (pintype "passive"))
      (node (ref "R6") (pin "1") (pinfunction "1_1") (pintype "passive"))
      (node (ref "R61") (pin "1") (pinfunction "1_1") (pintype "passive"))
      (node (ref "R66") (pin "1") (pinfunction "1_1") (pintype "passive"))
      (node (ref "R7") (pin "1") (pinfunction "1_1") (pintype "passive"))
      (node (ref "U51") (pin "B10") (pinfunction "GND_B10") (pintype "power_in"))
      (node (ref "U51") (pin "B12") (pinfunction "GND_B12") (pintype "power_in"))
      (node (ref "U51") (pin "B3") (pinfunction "GND_B3") (pintype "power_in"))
      (node (ref "U51") (pin "D3") (pinfunction "GND_D3") (pintype "power_in"))
      (node (ref "U51") (pin "D7") (pinfunction "GND_D7") (pintype "power_in"))
      (node (ref "U51") (pin "E11") (pinfunction "GND_E11") (pintype "power_in"))
      (node (ref "U51") (pin "G11") (pinfunction "GND_G11") (pintype "power_in"))
      (node (ref "U51") (pin "H10") (pinfunction "GND_H10") (pintype "power_in"))
      (node (ref "U51") (pin "J4") (pinfunction "GND_J4") (pintype "power_in"))
      (node (ref "U51") (pin "L11") (pinfunction "GND_L11") (pintype "power_in"))
      (node (ref "U51") (pin "L7") (pinfunction "GND_L7") (pintype "power_in"))
      (node (ref "U51") (pin "N11") (pinfunction "GND_N11") (pintype "power_in"))
      (node (ref "U8") (pin "21") (pinfunction "GND_21") (pintype "power_in"))
      (node (ref "U8") (pin "27") (pinfunction "OE#_27") (pintype "power_in"))
      (node (ref "U8") (pin "35") (pinfunction "GND_35") (pintype "power_in"))
      (node (ref "U8") (pin "40") (pinfunction "GND_40") (pintype "power_in"))
    )
    (net (code "106") (name "Net-(C30--)") (class "Default")
      (node (ref "C30") (pin "2") (pinfunction "-_2") (pintype "passive"))
      (node (ref "C36") (pin "2") (pinfunction "-_2") (pintype "passive"))
      (node (ref "C48") (pin "1") (pinfunction "+_1") (pintype "passive"))
      (node (ref "L3") (pin "2") (pinfunction "-_2") (pintype "passive"))
      (node (ref "U51") (pin "N12") (pinfunction "CVCC2_N12") (pintype "power_in"))
    )
    (net (code "107") (name "Net-(C171-+)") (class "Default")
      (node (ref "C171") (pin "1") (pinfunction "+_1") (pintype "passive"))
      (node (ref "J2") (pin "6") (pinfunction "Pin_6_6") (pintype "passive"))
      (node (ref "L16") (pin "1") (pinfunction "+_1") (pintype "passive"))
    )
    (net (code "108") (name "Net-(C176-+)") (class "Default")
      (node (ref "C176") (pin "1") (pinfunction "+_1") (pintype "passive"))
      (node (ref "C188") (pin "1") (pinfunction "+_1") (pintype "passive"))
      (node (ref "J2") (pin "4") (pinfunction "Pin_4_4") (pintype "passive"))
      (node (ref "L9") (pin "1") (pinfunction "+_1") (pintype "passive"))
      (node (ref "R234") (pin "2") (pinfunction "2_2") (pintype "passive"))
    )
    (net (code "109") (name "Net-(C177--)") (class "Default")
      (node (ref "C177") (pin "2") (pinfunction "-_2") (pintype "passive"))
      (node (ref "J2") (pin "27") (pinfunction "Pin_27_27") (pintype "passive"))
      (node (ref "L18") (pin "1") (pinfunction "+_1") (pintype "passive"))
    )
    (net (code "110") (name "Net-(C189--)") (class "Default")
      (node (ref "C189") (pin "2") (pinfunction "-_2") (pintype "passive"))
      (node (ref "J2") (pin "2") (pinfunction "Pin_2_2") (pintype "passive"))
      (node (ref "L14") (pin "1") (pinfunction "+_1") (pintype "passive"))
    )
    (net (code "111") (name "Net-(C192-+)") (class "Default")
      (node (ref "C192") (pin "1") (pinfunction "+_1") (pintype "passive"))
      (node (ref "J2") (pin "26") (pinfunction "Pin_26_26") (pintype "passive"))
      (node (ref "L11") (pin "2") (pinfunction "-_2") (pintype "passive"))
    )
    (net (code "112") (name "Net-(C193-+)") (class "Default")
      (node (ref "C193") (pin "1") (pinfunction "+_1") (pintype "passive"))
      (node (ref "J2") (pin "5") (pinfunction "Pin_5_5") (pintype "passive"))
      (node (ref "R234") (pin "1") (pinfunction "1_1") (pintype "passive"))
    )
    (net (code "113") (name "Net-(C195--)") (class "Default")
      (node (ref "C195") (pin "2") (pinfunction "-_2") (pintype "passive"))
      (node (ref "J2") (pin "29") (pinfunction "Pin_29_29") (pintype "passive"))
      (node (ref "L17") (pin "2") (pinfunction "-_2") (pintype "passive"))
    )
    (net (code "114") (name "Net-(C206--)") (class "Default")
      (node (ref "C206") (pin "2") (pinfunction "-_2") (pintype "passive"))
      (node (ref "C210") (pin "2") (pinfunction "-_2") (pintype "passive"))
      (node (ref "C45") (pin "1") (pinfunction "+_1") (pintype "passive"))
      (node (ref "L6") (pin "1") (pinfunction "+_1") (pintype "passive"))
      (node (ref "U51") (pin "M11") (pinfunction "CVCC_M11") (pintype "power_in"))
    )
    (net (code "115") (name "Net-(D2-A)") (class "Default")
      (node (ref "D2") (pin "2") (pinfunction "A_2") (pintype "passive"))
      (node (ref "R3") (pin "1") (pinfunction "1_1") (pintype "passive"))
    )
    (net (code "116") (name "Net-(D2-K)") (class "Default")
      (node (ref "D2") (pin "1") (pinfunction "K_1") (pintype "passive"))
      (node (ref "R12") (pin "2") (pinfunction "2_2") (pintype "passive"))
      (node (ref "U51") (pin "A11") (pinfunction "ENAVDD_A11") (pintype "output"))
    )
    (net (code "117") (name "Net-(D2-common)") (class "Default")
      (node (ref "D2") (pin "3") (pinfunction "common_3") (pintype "passive"))
      (node (ref "Q2") (pin "1") (pinfunction "B_1") (pintype "input"))
      (node (ref "R12") (pin "1") (pinfunction "1_1") (pintype "passive"))
    )
    (net (code "118") (name "Net-(D36-K)") (class "Default")
      (node (ref "D36") (pin "1") (pinfunction "K_1") (pintype "passive"))
      (node (ref "L14") (pin "2") (pinfunction "-_2") (pintype "passive"))
      (node (ref "R236") (pin "2") (pinfunction "2_2") (pintype "passive"))
    )
    (net (code "119") (name "Net-(J2-Pin_1)") (class "Default")
      (node (ref "J2") (pin "1") (pinfunction "Pin_1_1") (pintype "passive"))
      (node (ref "J2") (pin "16") (pinfunction "Pin_16_16") (pintype "passive"))
      (node (ref "J2") (pin "25") (pinfunction "Pin_25_25") (pintype "passive"))
      (node (ref "J2") (pin "28") (pinfunction "Pin_28_28") (pintype "passive"))
      (node (ref "J2") (pin "30") (pinfunction "Pin_30_30") (pintype "passive"))
      (node (ref "J2") (pin "7") (pinfunction "Pin_7_7") (pintype "passive"))
      (node (ref "L10") (pin "1") (pinfunction "+_1") (pintype "passive"))
    )
    (net (code "120") (name "Net-(L9--)") (class "Default")
      (node (ref "L9") (pin "2") (pinfunction "-_2") (pintype "passive"))
      (node (ref "Q1") (pin "3") (pinfunction "C_3") (pintype "passive"))
      (node (ref "R236") (pin "1") (pinfunction "1_1") (pintype "passive"))
      (node (ref "R3") (pin "2") (pinfunction "2_2") (pintype "passive"))
    )
    (net (code "121") (name "Net-(L11-+)") (class "Default")
      (node (ref "L11") (pin "1") (pinfunction "+_1") (pintype "passive"))
      (node (ref "R14") (pin "2") (pinfunction "2_2") (pintype "passive"))
    )
    (net (code "122") (name "Net-(L17-+)") (class "Default")
      (node (ref "L17") (pin "1") (pinfunction "+_1") (pintype "passive"))
      (node (ref "R20") (pin "2") (pinfunction "2_2") (pintype "passive"))
    )
    (net (code "123") (name "Net-(L18--)") (class "Default")
      (node (ref "L18") (pin "2") (pinfunction "-_2") (pintype "passive"))
      (node (ref "R17") (pin "2") (pinfunction "2_2") (pintype "passive"))
    )
    (net (code "124") (name "Net-(Q1-B)") (class "Default")
      (node (ref "Q1") (pin "1") (pinfunction "B_1") (pintype "input"))
      (node (ref "R9") (pin "2") (pinfunction "2_2") (pintype "passive"))
    )
    (net (code "125") (name "Net-(Q2-C)") (class "Default")
      (node (ref "Q2") (pin "3") (pinfunction "C_3") (pintype "passive"))
      (node (ref "R9") (pin "1") (pinfunction "1_1") (pintype "passive"))
    )
    (net (code "126") (name "Net-(U8-LCAS#)") (class "Default")
      (node (ref "R58") (pin "2") (pinfunction "2_2") (pintype "passive"))
      (node (ref "U8") (pin "29") (pinfunction "LCAS#_29") (pintype "input"))
    )
    (net (code "127") (name "Net-(U8-RAS#)") (class "Default")
      (node (ref "R21") (pin "1") (pinfunction "1_1") (pintype "passive"))
      (node (ref "U8") (pin "14") (pinfunction "RAS#_14") (pintype "input"))
    )
    (net (code "128") (name "Net-(U8-UCAS#)") (class "Default")
      (node (ref "R51") (pin "2") (pinfunction "2_2") (pintype "passive"))
      (node (ref "U8") (pin "28") (pinfunction "UCAS#_28") (pintype "input"))
    )
    (net (code "129") (name "Net-(U8-WE#)") (class "Default")
      (node (ref "R16") (pin "1") (pinfunction "1_1") (pintype "passive"))
      (node (ref "U8") (pin "13") (pinfunction "WE#_13") (pintype "input"))
    )
    (net (code "130") (name "Net-(U51-CASAH#)") (class "Default")
      (node (ref "R51") (pin "1") (pinfunction "1_1") (pintype "passive"))
      (node (ref "U51") (pin "J3") (pinfunction "CASAH#_J3") (pintype "output"))
    )
    (net (code "131") (name "Net-(U51-CASAL#)") (class "Default")
      (node (ref "R58") (pin "1") (pinfunction "1_1") (pintype "passive"))
      (node (ref "U51") (pin "K2") (pinfunction "CASAL#_K2") (pintype "output"))
    )
    (net (code "132") (name "Net-(U51-CCLK)") (class "Default")
      (node (ref "R255") (pin "2") (pinfunction "2_2") (pintype "passive"))
      (node (ref "U51") (pin "E10") (pinfunction "CCLK_E10") (pintype "input"))
    )
    (net (code "133") (name "Net-(U51-FLM)") (class "Default")
      (node (ref "R14") (pin "1") (pinfunction "1_1") (pintype "passive"))
      (node (ref "U51") (pin "B9") (pinfunction "FLM_B9") (pintype "output"))
    )
    (net (code "134") (name "Net-(U51-HSYNC)") (class "Default")
      (node (ref "R53") (pin "2") (pinfunction "2_2") (pintype "passive"))
      (node (ref "U51") (pin "A10") (pinfunction "HSYNC_A10") (pintype "output"))
    )
    (net (code "135") (name "Net-(U51-IO0)") (class "Default")
      (node (ref "R11") (pin "1") (pinfunction "1_1") (pintype "passive"))
      (node (ref "U51") (pin "L1") (pinfunction "IO0_L1") (pintype "bidirectional"))
      (node (ref "U8") (pin "2") (pinfunction "DQ0_2") (pintype "bidirectional"))
    )
    (net (code "136") (name "Net-(U51-IO1)") (class "Default")
      (node (ref "R1") (pin "2") (pinfunction "2_2") (pintype "passive"))
      (node (ref "U51") (pin "K3") (pinfunction "IO1_K3") (pintype "bidirectional"))
      (node (ref "U8") (pin "3") (pinfunction "DQ1_3") (pintype "bidirectional"))
    )
    (net (code "137") (name "Net-(U51-IO2)") (class "Default")
      (node (ref "R10") (pin "2") (pinfunction "2_2") (pintype "passive"))
      (node (ref "U51") (pin "L2") (pinfunction "IO2_L2") (pintype "bidirectional"))
      (node (ref "U8") (pin "4") (pinfunction "DQ2_4") (pintype "bidirectional"))
    )
    (net (code "138") (name "Net-(U51-IO3)") (class "Default")
      (node (ref "R6") (pin "2") (pinfunction "2_2") (pintype "passive"))
      (node (ref "U51") (pin "K4") (pinfunction "IO3_K4") (pintype "bidirectional"))
      (node (ref "U8") (pin "5") (pinfunction "DQ3_5") (pintype "bidirectional"))
    )
    (net (code "139") (name "Net-(U51-IO4)") (class "Default")
      (node (ref "R7") (pin "2") (pinfunction "2_2") (pintype "passive"))
      (node (ref "U51") (pin "L3") (pinfunction "IO4_L3") (pintype "bidirectional"))
      (node (ref "U8") (pin "7") (pinfunction "DQ4_7") (pintype "bidirectional"))
    )
    (net (code "140") (name "Net-(U51-IO5)") (class "Default")
      (node (ref "R13") (pin "2") (pinfunction "2_2") (pintype "passive"))
      (node (ref "U51") (pin "N1") (pinfunction "IO5_N1") (pintype "bidirectional"))
      (node (ref "U8") (pin "8") (pinfunction "DQ5_8") (pintype "bidirectional"))
    )
    (net (code "141") (name "Net-(U51-IO6)") (class "Default")
      (node (ref "R5") (pin "2") (pinfunction "2_2") (pintype "passive"))
      (node (ref "U51") (pin "M2") (pinfunction "IO6_M2") (pintype "bidirectional"))
      (node (ref "U8") (pin "9") (pinfunction "DQ6_9") (pintype "bidirectional"))
    )
    (net (code "142") (name "Net-(U51-IO7)") (class "Default")
      (node (ref "R2") (pin "2") (pinfunction "2_2") (pintype "passive"))
      (node (ref "U51") (pin "L4") (pinfunction "IO7_L4") (pintype "bidirectional"))
      (node (ref "U8") (pin "10") (pinfunction "DQ7_10") (pintype "bidirectional"))
    )
    (net (code "143") (name "Net-(U51-IO8)") (class "Default")
      (node (ref "R269") (pin "1") (pinfunction "1_1") (pintype "passive"))
      (node (ref "U51") (pin "N2") (pinfunction "IO8_N2") (pintype "bidirectional"))
      (node (ref "U8") (pin "31") (pinfunction "DQ8_31") (pintype "bidirectional"))
    )
    (net (code "144") (name "Net-(U51-IO9)") (class "Default")
      (node (ref "R259") (pin "1") (pinfunction "1_1") (pintype "passive"))
      (node (ref "U51") (pin "M3") (pinfunction "IO9_M3") (pintype "bidirectional"))
      (node (ref "U8") (pin "32") (pinfunction "DQ9_32") (pintype "bidirectional"))
    )
    (net (code "145") (name "Net-(U51-IO10)") (class "Default")
      (node (ref "R61") (pin "2") (pinfunction "2_2") (pintype "passive"))
      (node (ref "U51") (pin "K5") (pinfunction "IO10_K5") (pintype "bidirectional"))
      (node (ref "U8") (pin "33") (pinfunction "DQ10_33") (pintype "bidirectional"))
    )
    (net (code "146") (name "Net-(U51-IO11)") (class "Default")
      (node (ref "R18") (pin "1") (pinfunction "1_1") (pintype "passive"))
      (node (ref "U51") (pin "J5") (pinfunction "IO11_J5") (pintype "bidirectional"))
      (node (ref "U8") (pin "34") (pinfunction "DQ11_34") (pintype "bidirectional"))
    )
    (net (code "147") (name "Net-(U51-IO12)") (class "Default")
      (node (ref "R15") (pin "1") (pinfunction "1_1") (pintype "passive"))
      (node (ref "U51") (pin "N3") (pinfunction "IO12_N3") (pintype "bidirectional"))
      (node (ref "U8") (pin "36") (pinfunction "DQ12_36") (pintype "bidirectional"))
    )
    (net (code "148") (name "Net-(U51-IO13)") (class "Default")
      (node (ref "R22") (pin "2") (pinfunction "2_2") (pintype "passive"))
      (node (ref "U51") (pin "M4") (pinfunction "IO13_M4") (pintype "bidirectional"))
      (node (ref "U8") (pin "37") (pinfunction "DQ13_37") (pintype "bidirectional"))
    )
    (net (code "149") (name "Net-(U51-IO14)") (class "Default")
      (node (ref "R233") (pin "1") (pinfunction "1_1") (pintype "passive"))
      (node (ref "U51") (pin "L5") (pinfunction "IO14_L5") (pintype "bidirectional"))
      (node (ref "U8") (pin "38") (pinfunction "DQ14_38") (pintype "bidirectional"))
    )
    (net (code "150") (name "Net-(U51-IO15)") (class "Default")
      (node (ref "R19") (pin "2") (pinfunction "2_2") (pintype "passive"))
      (node (ref "U51") (pin "N4") (pinfunction "IO15_N4") (pintype "bidirectional"))
      (node (ref "U8") (pin "39") (pinfunction "DQ15_39") (pintype "bidirectional"))
    )
    (net (code "151") (name "Net-(U51-LP)") (class "Default")
      (node (ref "R17") (pin "1") (pinfunction "1_1") (pintype "passive"))
      (node (ref "U51") (pin "A9") (pinfunction "LP_A9") (pintype "output"))
    )
    (net (code "152") (name "Net-(U51-OEL#)") (class "Default")
      (node (ref "R263") (pin "1") (pinfunction "1_1") (pintype "passive"))
      (node (ref "U51") (pin "B13") (pinfunction "OEL#_B13") (pintype "output"))
    )
    (net (code "153") (name "Net-(U51-P0)") (class "Default")
      (node (ref "EM1") (pin "5") (pinfunction "5_5") (pintype "passive"))
      (node (ref "U51") (pin "E8") (pinfunction "P0_E8") (pintype "output"))
    )
    (net (code "154") (name "Net-(U51-P1)") (class "Default")
      (node (ref "EM1") (pin "6") (pinfunction "6_6") (pintype "passive"))
      (node (ref "U51") (pin "A8") (pinfunction "P1_A8") (pintype "output"))
    )
    (net (code "155") (name "Net-(U51-P2)") (class "Default")
      (node (ref "EM1") (pin "7") (pinfunction "7_7") (pintype "passive"))
      (node (ref "U51") (pin "B7") (pinfunction "P2_B7") (pintype "output"))
    )
    (net (code "156") (name "Net-(U51-P3)") (class "Default")
      (node (ref "EM1") (pin "8") (pinfunction "8_8") (pintype "passive"))
      (node (ref "U51") (pin "A7") (pinfunction "P3_A7") (pintype "output"))
    )
    (net (code "157") (name "Net-(U51-P4)") (class "Default")
      (node (ref "EM3") (pin "5") (pinfunction "5_5") (pintype "passive"))
      (node (ref "U51") (pin "E7") (pinfunction "P4_E7") (pintype "output"))
    )
    (net (code "158") (name "Net-(U51-P5)") (class "Default")
      (node (ref "EM3") (pin "6") (pinfunction "6_6") (pintype "passive"))
      (node (ref "U51") (pin "A6") (pinfunction "P5_A6") (pintype "output"))
    )
    (net (code "159") (name "Net-(U51-P6)") (class "Default")
      (node (ref "EM3") (pin "7") (pinfunction "7_7") (pintype "passive"))
      (node (ref "U51") (pin "B6") (pinfunction "P6_B6") (pintype "output"))
    )
    (net (code "160") (name "Net-(U51-P7)") (class "Default")
      (node (ref "EM3") (pin "8") (pinfunction "8_8") (pintype "passive"))
      (node (ref "U51") (pin "E6") (pinfunction "P7_E6") (pintype "output"))
    )
    (net (code "161") (name "Net-(U51-P8)") (class "Default")
      (node (ref "EM2") (pin "5") (pinfunction "5_5") (pintype "passive"))
      (node (ref "U51") (pin "C6") (pinfunction "P8_C6") (pintype "output"))
    )
    (net (code "162") (name "Net-(U51-P9)") (class "Default")
      (node (ref "EM2") (pin "6") (pinfunction "6_6") (pintype "passive"))
      (node (ref "U51") (pin "A5") (pinfunction "P9_A5") (pintype "output"))
    )
    (net (code "163") (name "Net-(U51-P10)") (class "Default")
      (node (ref "EM2") (pin "7") (pinfunction "7_7") (pintype "passive"))
      (node (ref "U51") (pin "B5") (pinfunction "P10_B5") (pintype "output"))
    )
    (net (code "164") (name "Net-(U51-P11)") (class "Default")
      (node (ref "EM2") (pin "8") (pinfunction "8_8") (pintype "passive"))
      (node (ref "U51") (pin "D6") (pinfunction "P11_D6") (pintype "output"))
    )
    (net (code "165") (name "Net-(U51-P12)") (class "Default")
      (node (ref "EM4") (pin "5") (pinfunction "5_5") (pintype "passive"))
      (node (ref "U51") (pin "A4") (pinfunction "P12_A4") (pintype "output"))
    )
    (net (code "166") (name "Net-(U51-P13)") (class "Default")
      (node (ref "EM4") (pin "6") (pinfunction "6_6") (pintype "passive"))
      (node (ref "U51") (pin "C5") (pinfunction "P13_C5") (pintype "output"))
    )
    (net (code "167") (name "Net-(U51-P14)") (class "Default")
      (node (ref "EM4") (pin "7") (pinfunction "7_7") (pintype "passive"))
      (node (ref "U51") (pin "B4") (pinfunction "P14_B4") (pintype "output"))
    )
    (net (code "168") (name "Net-(U51-P15)") (class "Default")
      (node (ref "EM4") (pin "8") (pinfunction "8_8") (pintype "passive"))
      (node (ref "U51") (pin "A3") (pinfunction "P15_A3") (pintype "output"))
    )
    (net (code "169") (name "Net-(U51-RASA#)") (class "Default")
      (node (ref "R21") (pin "2") (pinfunction "2_2") (pintype "passive"))
      (node (ref "U51") (pin "H4") (pinfunction "RASA#_H4") (pintype "output"))
    )
    (net (code "170") (name "Net-(U51-RSET)") (class "Default")
      (node (ref "R66") (pin "2") (pinfunction "2_2") (pintype "passive"))
      (node (ref "U51") (pin "A13") (pinfunction "RSET_A13") (pintype "input"))
    )
    (net (code "171") (name "Net-(U51-SA0)") (class "Default")
      (node (ref "R265") (pin "1") (pinfunction "1_1") (pintype "passive"))
      (node (ref "U51") (pin "G2") (pinfunction "SA0_G2") (pintype "bidirectional"))
      (node (ref "U8") (pin "16") (pinfunction "A0_16") (pintype "input"))
    )
    (net (code "172") (name "Net-(U51-SA1)") (class "Default")
      (node (ref "U51") (pin "G1") (pinfunction "SA1_G1") (pintype "bidirectional"))
      (node (ref "U8") (pin "17") (pinfunction "A1_17") (pintype "input"))
    )
    (net (code "173") (name "Net-(U51-SA2)") (class "Default")
      (node (ref "U51") (pin "G3") (pinfunction "SA2_G3") (pintype "bidirectional"))
      (node (ref "U8") (pin "18") (pinfunction "A2_18") (pintype "input"))
    )
    (net (code "174") (name "Net-(U51-SA3)") (class "Default")
      (node (ref "U51") (pin "G5") (pinfunction "SA3_G5") (pintype "bidirectional"))
      (node (ref "U8") (pin "19") (pinfunction "A3_19") (pintype "input"))
    )
    (net (code "175") (name "Net-(U51-SA4)") (class "Default")
      (node (ref "U51") (pin "H1") (pinfunction "SA4_H1") (pintype "bidirectional"))
      (node (ref "U8") (pin "22") (pinfunction "A4_22") (pintype "input"))
    )
    (net (code "176") (name "Net-(U51-SA5)") (class "Default")
      (node (ref "R270") (pin "1") (pinfunction "1_1") (pintype "passive"))
      (node (ref "U51") (pin "H2") (pinfunction "SA5_H2") (pintype "bidirectional"))
      (node (ref "U8") (pin "23") (pinfunction "A5_23") (pintype "input"))
    )
    (net (code "177") (name "Net-(U51-SA6)") (class "Default")
      (node (ref "U51") (pin "H5") (pinfunction "SA6_H5") (pintype "bidirectional"))
      (node (ref "U8") (pin "24") (pinfunction "A6_24") (pintype "input"))
    )
    (net (code "178") (name "Net-(U51-SA7)") (class "Default")
      (node (ref "U51") (pin "H3") (pinfunction "SA7_H3") (pintype "bidirectional"))
      (node (ref "U8") (pin "25") (pinfunction "A7_25") (pintype "input"))
    )
    (net (code "179") (name "Net-(U51-SA8)") (class "Default")
      (node (ref "R279") (pin "1") (pinfunction "1_1") (pintype "passive"))
      (node (ref "U51") (pin "J1") (pinfunction "SA8_J1") (pintype "bidirectional"))
      (node (ref "U8") (pin "26") (pinfunction "A8_26") (pintype "input"))
    )
    (net (code "180") (name "Net-(U51-SHFCLK)") (class "Default")
      (node (ref "R20") (pin "1") (pinfunction "1_1") (pintype "passive"))
      (node (ref "U51") (pin "B8") (pinfunction "SHFCLK_B8") (pintype "output"))
    )
    (net (code "181") (name "Net-(U51-VSYNC)") (class "Default")
      (node (ref "R46") (pin "2") (pinfunction "2_2") (pintype "passive"))
      (node (ref "U51") (pin "C9") (pinfunction "VSYNC_C9") (pintype "output"))
    )
    (net (code "182") (name "Net-(U51-WEA#)") (class "Default")
      (node (ref "R16") (pin "2") (pinfunction "2_2") (pintype "passive"))
      (node (ref "U51") (pin "K1") (pinfunction "WEA#_K1") (pintype "output"))
    )
    (net (code "183") (name "PNET1") (class "Default")
      (node (ref "C156") (pin "2") (pinfunction "-_2") (pintype "passive"))
      (node (ref "C17") (pin "1") (pinfunction "+_1") (pintype "passive"))
      (node (ref "C172") (pin "2") (pinfunction "-_2") (pintype "passive"))
      (node (ref "C26") (pin "1") (pinfunction "+_1") (pintype "passive"))
      (node (ref "C31") (pin "2") (pinfunction "-_2") (pintype "passive"))
      (node (ref "C32") (pin "1") (pinfunction "+_1") (pintype "passive"))
      (node (ref "C34") (pin "1") (pinfunction "+_1") (pintype "passive"))
      (node (ref "C37") (pin "1") (pinfunction "+_1") (pintype "passive"))
      (node (ref "C38") (pin "1") (pinfunction "+_1") (pintype "passive"))
      (node (ref "C39") (pin "1") (pinfunction "+_1") (pintype "passive"))
      (node (ref "C40") (pin "1") (pinfunction "+_1") (pintype "passive"))
      (node (ref "C41") (pin "1") (pinfunction "+_1") (pintype "passive"))
      (node (ref "C42") (pin "2") (pinfunction "-_2") (pintype "passive"))
      (node (ref "C43") (pin "1") (pinfunction "+_1") (pintype "passive"))
      (node (ref "C5") (pin "1") (pinfunction "+_1") (pintype "passive"))
      (node (ref "L3") (pin "1") (pinfunction "+_1") (pintype "passive"))
      (node (ref "L6") (pin "2") (pinfunction "-_2") (pintype "passive"))
      (node (ref "R229") (pin "2") (pinfunction "2_2") (pintype "passive"))
      (node (ref "U51") (pin "B11") (pinfunction "VCC_B11") (pintype "power_in"))
      (node (ref "U51") (pin "C7") (pinfunction "VCC_C7") (pintype "power_in"))
      (node (ref "U51") (pin "D8") (pinfunction "VCC_D8") (pintype "power_in"))
      (node (ref "U51") (pin "E12") (pinfunction "VCC_E12") (pintype "power_in"))
      (node (ref "U51") (pin "E4") (pinfunction "VCC_E4") (pintype "power_in"))
      (node (ref "U51") (pin "G10") (pinfunction "VCC_G10") (pintype "power_in"))
      (node (ref "U51") (pin "K6") (pinfunction "VCC_K6") (pintype "power_in"))
      (node (ref "U51") (pin "K7") (pinfunction "VCC_K7") (pintype "power_in"))
      (node (ref "U51") (pin "M1") (pinfunction "VCC_M1") (pintype "power_in"))
      (node (ref "U8") (pin "1") (pinfunction "VCC_1") (pintype "power_in"))
      (node (ref "U8") (pin "20") (pinfunction "VCC_20") (pintype "power_in"))
      (node (ref "U8") (pin "6") (pinfunction "VCC_6") (pintype "power_in"))
    )
    (net (code "184") (name "PNET5") (class "Default")
      (node (ref "Q1") (pin "2") (pinfunction "E_2") (pintype "passive"))
    )
    (net (code "185") (name "unconnected-(U8-NC-Pad11)") (class "Default")
      (node (ref "U8") (pin "11") (pinfunction "NC_11") (pintype "input"))
    )
    (net (code "186") (name "unconnected-(U8-NC-Pad12)") (class "Default")
      (node (ref "U8") (pin "12") (pinfunction "NC_12") (pintype "input"))
    )
    (net (code "187") (name "unconnected-(U8-NC-Pad15)") (class "Default")
      (node (ref "U8") (pin "15") (pinfunction "NC_15") (pintype "input"))
    )
    (net (code "188") (name "unconnected-(U8-NC-Pad30)") (class "Default")
      (node (ref "U8") (pin "30") (pinfunction "NC_30") (pintype "input"))
    )
    (net (code "189") (name "unconnected-(U51-ACTI-PadD5)") (class "Default")
      (node (ref "U51") (pin "D5") (pinfunction "ACTI_D5") (pintype "bidirectional+no_connect"))
    )
    (net (code "190") (name "unconnected-(U51-CASBH#-PadC3)") (class "Default")
      (node (ref "U51") (pin "C3") (pinfunction "CASBH#_C3") (pintype "output+no_connect"))
    )
    (net (code "191") (name "unconnected-(U51-CASBL#-PadA1)") (class "Default")
      (node (ref "U51") (pin "A1") (pinfunction "CASBL#_A1") (pintype "output+no_connect"))
    )
    (net (code "192") (name "unconnected-(U51-ENABKL-PadC4)") (class "Default")
      (node (ref "U51") (pin "C4") (pinfunction "ENABKL_C4") (pintype "bidirectional+no_connect"))
    )
    (net (code "193") (name "unconnected-(U51-M-PadC8)") (class "Default")
      (node (ref "U51") (pin "C8") (pinfunction "M_C8") (pintype "output+no_connect"))
    )
    (net (code "194") (name "unconnected-(U51-OEH#-PadD10)") (class "Default")
      (node (ref "U51") (pin "D10") (pinfunction "OEH#_D10") (pintype "output+no_connect"))
    )
    (net (code "195") (name "unconnected-(U51-PadF6)") (class "Default")
      (node (ref "U51") (pin "F6") (pinfunction "F6_F6") (pintype "input"))
    )
    (net (code "196") (name "unconnected-(U51-PadF7)") (class "Default")
      (node (ref "U51") (pin "F7") (pinfunction "F7_F7") (pintype "input"))
    )
    (net (code "197") (name "unconnected-(U51-PadF8)") (class "Default")
      (node (ref "U51") (pin "F8") (pinfunction "F8_F8") (pintype "input"))
    )
    (net (code "198") (name "unconnected-(U51-PadG6)") (class "Default")
      (node (ref "U51") (pin "G6") (pinfunction "G6_G6") (pintype "input"))
    )
    (net (code "199") (name "unconnected-(U51-PadG7)") (class "Default")
      (node (ref "U51") (pin "G7") (pinfunction "G7_G7") (pintype "input"))
    )
    (net (code "200") (name "unconnected-(U51-PadG8)") (class "Default")
      (node (ref "U51") (pin "G8") (pinfunction "G8_G8") (pintype "input"))
    )
    (net (code "201") (name "unconnected-(U51-PadH6)") (class "Default")
      (node (ref "U51") (pin "H6") (pinfunction "H6_H6") (pintype "input"))
    )
    (net (code "202") (name "unconnected-(U51-PadH7)") (class "Default")
      (node (ref "U51") (pin "H7") (pinfunction "H7_H7") (pintype "input"))
    )
    (net (code "203") (name "unconnected-(U51-PadH8)") (class "Default")
      (node (ref "U51") (pin "H8") (pinfunction "H8_H8") (pintype "input"))
    )
    (net (code "204") (name "unconnected-(U51-RASB#-PadA2)") (class "Default")
      (node (ref "U51") (pin "A2") (pinfunction "RASB#_A2") (pintype "output+no_connect"))
    )
    (net (code "205") (name "unconnected-(U51-WEB#-PadD4)") (class "Default")
      (node (ref "U51") (pin "D4") (pinfunction "WEB#_D4") (pintype "input+no_connect"))
    )
    (net (code "206") (name "unconnected-(U51-XTAL0-PadL10)") (class "Default")
      (node (ref "U51") (pin "L10") (pinfunction "XTAL0_L10") (pintype "output+no_connect"))
    )
  )
)
